# Communicate.net
KiCad netlist of a schematic drawn in Altium Designer
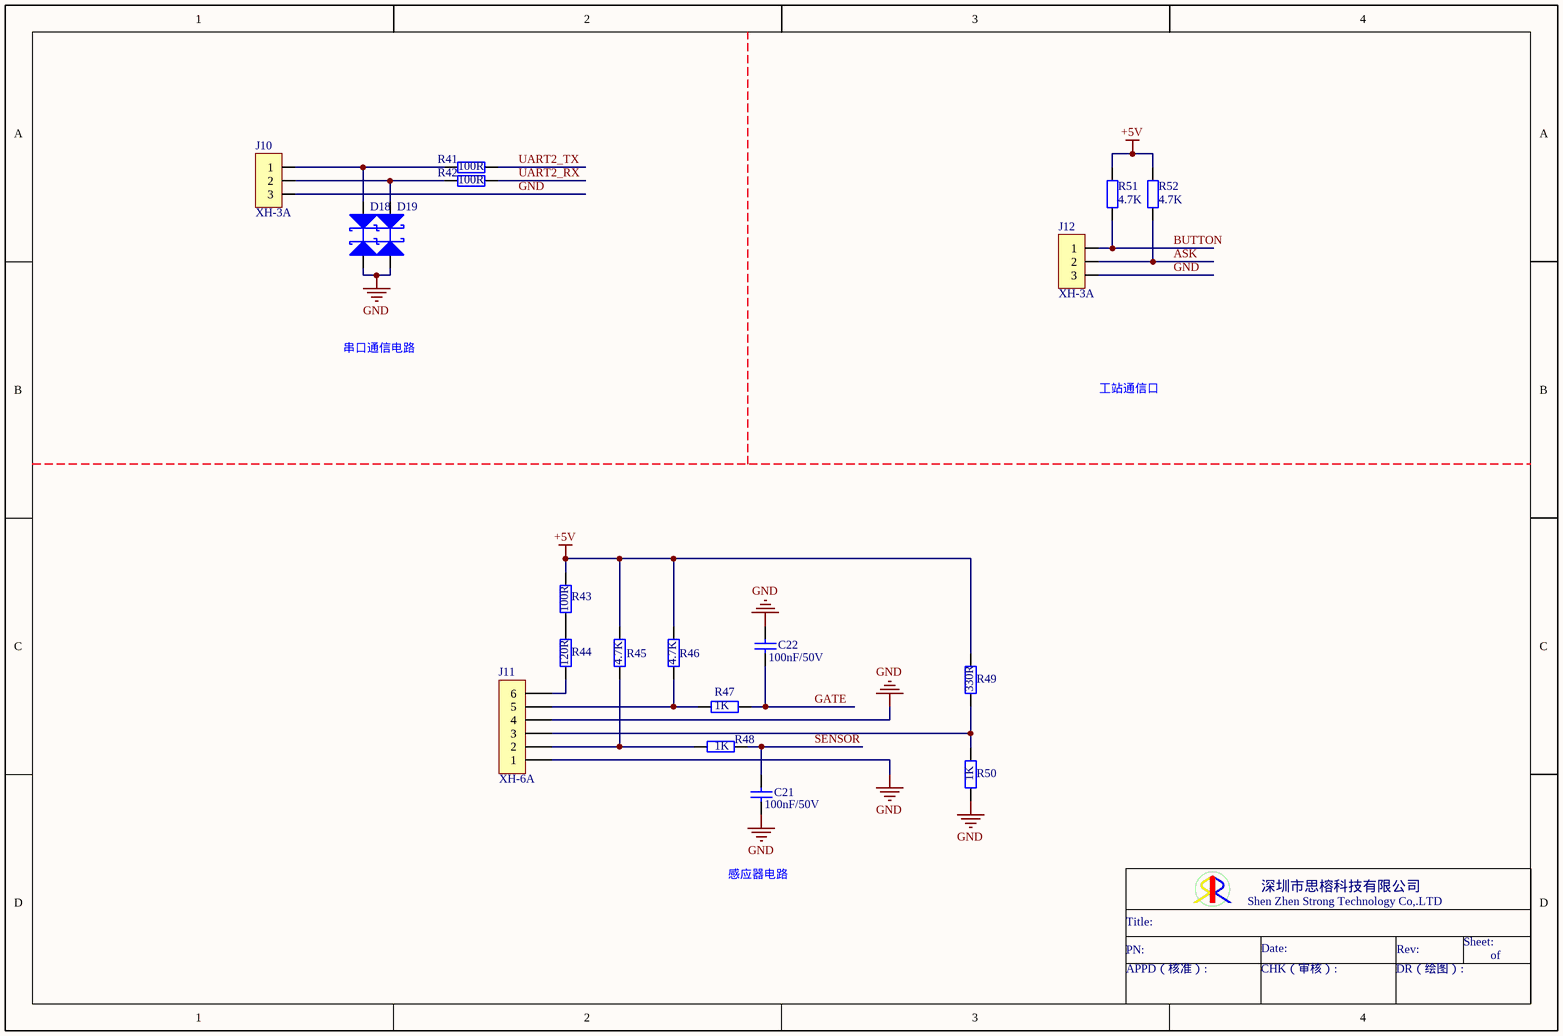
[diagram p0: Communicate.SchDoc]

(export (version "E")
  (design (tool "Eeschema 10.0.6"))
  (components
    (comp (ref "C21")
      (value "100nF/50V")
      (footprint "0603C")
      (description "瓷片电容,100nF,5%,X7R,50V,0603")
      (libsource (lib "SR SCH Library V02") (part "C100nF/50V-0603"))
    )
    (comp (ref "C22")
      (value "100nF/50V")
      (footprint "0603C")
      (description "瓷片电容,100nF,5%,X7R,50V,0603")
      (libsource (lib "SR SCH Library V02") (part "C100nF/50V-0603"))
    )
    (comp (ref "D18")
      (value "ESD5B5.0ST1G")
      (footprint "SOD-523")
      (description "TVS管,5V,SOD-523")
      (libsource (lib "SR SCH Library V02") (part "ESD5B5.0ST1G"))
    )
    (comp (ref "D19")
      (value "ESD5B5.0ST1G")
      (footprint "SOD-523")
      (description "TVS管,5V,SOD-523")
      (libsource (lib "SR SCH Library V02") (part "ESD5B5.0ST1G"))
    )
    (comp (ref "J10")
      (value "XH-3A")
      (footprint "CN3-2.54")
      (description "CONN,XH-3A,3PIN,2.54mm插座")
      (libsource (lib "SR SCH Library V02") (part "CONN-XH-3A"))
    )
    (comp (ref "J11")
      (value "XH-6A")
      (footprint "CN6-2.54")
      (description "CONN,XH-6A,6PIN,2.54mm插座")
      (libsource (lib "SR SCH Library V02") (part "CONN-XH-6A"))
    )
    (comp (ref "J12")
      (value "XH-3A")
      (footprint "CN3-2.54")
      (description "CONN,XH-3A,3PIN,2.54mm插座")
      (libsource (lib "SR SCH Library V02") (part "CONN-XH-3A"))
    )
    (comp (ref "R41")
      (value "100R")
      (footprint "0603R")
      (description "金属膜电阻,100R,1%,1/10W,0603")
      (libsource (lib "SR SCH Library V02") (part "R100R-0603"))
    )
    (comp (ref "R42")
      (value "100R")
      (footprint "0603R")
      (description "金属膜电阻,100R,1%,1/10W,0603")
      (libsource (lib "SR SCH Library V02") (part "R100R-0603"))
    )
    (comp (ref "R43")
      (value "100R")
      (footprint "0603R")
      (description "金属膜电阻,100R,1%,1/10W,0603")
      (libsource (lib "") (part "R100R-0603_1"))
    )
    (comp (ref "R44")
      (value "120R")
      (footprint "0603R")
      (description "金属膜电阻,120R,5W,5%")
      (libsource (lib "SR SCH Library V02") (part "R120R"))
    )
    (comp (ref "R45")
      (value "4.7K")
      (footprint "0603R")
      (description "金属膜电阻,4.7K,1%,1/10W,0603")
      (libsource (lib "SR SCH Library V02") (part "R4.7K-0603"))
    )
    (comp (ref "R46")
      (value "4.7K")
      (footprint "0603R")
      (description "金属膜电阻,4.7K,1%,1/10W,0603")
      (libsource (lib "SR SCH Library V02") (part "R4.7K-0603"))
    )
    (comp (ref "R47")
      (value "1K")
      (footprint "0603R")
      (description "金属膜电阻,1K,1%,1/10W,0603")
      (libsource (lib "SR SCH Library V02") (part "R1K-0603"))
    )
    (comp (ref "R48")
      (value "1K")
      (footprint "0603R")
      (description "金属膜电阻,1K,1%,1/10W,0603")
      (libsource (lib "SR SCH Library V02") (part "R1K-0603"))
    )
    (comp (ref "R49")
      (value "330R")
      (footprint "0603R")
      (description "金属膜电阻,330R,1%,1/10W,0603")
      (libsource (lib "SR SCH Library V02") (part "R330R-0603"))
    )
    (comp (ref "R50")
      (value "1K")
      (footprint "0603R")
      (description "金属膜电阻,1K,1%,1/10W,0603")
      (libsource (lib "") (part "R1K-0603_1"))
    )
    (comp (ref "R51")
      (value "4.7K")
      (footprint "0603R")
      (description "金属膜电阻,4.7K,1%,1/10W,0603")
      (libsource (lib "SR SCH Library V02") (part "R4.7K-0603"))
    )
    (comp (ref "R52")
      (value "4.7K")
      (footprint "0603R")
      (description "金属膜电阻,4.7K,1%,1/10W,0603")
      (libsource (lib "SR SCH Library V02") (part "R4.7K-0603"))
    )
  )
  (nets
    (net (code "1") (name "+5V") (class "Default")
      (node (ref "R43") (pin "2") (pinfunction "2_2") (pintype "passive"))
      (node (ref "R45") (pin "2") (pinfunction "2_2") (pintype "passive"))
      (node (ref "R46") (pin "2") (pinfunction "2_2") (pintype "passive"))
      (node (ref "R49") (pin "2") (pinfunction "2_2") (pintype "passive"))
      (node (ref "R51") (pin "2") (pinfunction "2_2") (pintype "passive"))
      (node (ref "R52") (pin "2") (pinfunction "2_2") (pintype "passive"))
    )
    (net (code "2") (name "/ASK") (class "Default")
      (node (ref "J12") (pin "2") (pinfunction "2_2") (pintype "passive"))
      (node (ref "R52") (pin "1") (pinfunction "1_1") (pintype "passive"))
    )
    (net (code "3") (name "/BUTTON") (class "Default")
      (node (ref "J12") (pin "1") (pinfunction "1_1") (pintype "passive"))
      (node (ref "R51") (pin "1") (pinfunction "1_1") (pintype "passive"))
    )
    (net (code "4") (name "/GATE") (class "Default")
      (node (ref "C22") (pin "2") (pinfunction "2_2") (pintype "passive"))
      (node (ref "R47") (pin "2") (pinfunction "2_2") (pintype "passive"))
    )
    (net (code "5") (name "/SENSOR") (class "Default")
      (node (ref "C21") (pin "2") (pinfunction "2_2") (pintype "passive"))
      (node (ref "R48") (pin "2") (pinfunction "2_2") (pintype "passive"))
    )
    (net (code "6") (name "/UART2_RX") (class "Default")
      (node (ref "R42") (pin "2") (pinfunction "2_2") (pintype "passive"))
    )
    (net (code "7") (name "/UART2_TX") (class "Default")
      (node (ref "R41") (pin "2") (pinfunction "2_2") (pintype "passive"))
    )
    (net (code "8") (name "GND") (class "Default")
      (node (ref "C21") (pin "1") (pinfunction "1_1") (pintype "passive"))
      (node (ref "C22") (pin "1") (pinfunction "1_1") (pintype "passive"))
      (node (ref "D18") (pin "1") (pinfunction "1_1") (pintype "passive"))
      (node (ref "D19") (pin "1") (pinfunction "1_1") (pintype "passive"))
      (node (ref "J10") (pin "3") (pinfunction "3_3") (pintype "passive"))
      (node (ref "J11") (pin "1") (pinfunction "1_1") (pintype "passive"))
      (node (ref "J11") (pin "4") (pinfunction "4_4") (pintype "passive"))
      (node (ref "J12") (pin "3") (pinfunction "3_3") (pintype "passive"))
      (node (ref "R50") (pin "1") (pinfunction "1_1") (pintype "passive"))
    )
    (net (code "9") (name "Net-(D18-Pad2)") (class "Default")
      (node (ref "D18") (pin "2") (pinfunction "2_2") (pintype "passive"))
      (node (ref "J10") (pin "1") (pinfunction "1_1") (pintype "passive"))
      (node (ref "R41") (pin "1") (pinfunction "1_1") (pintype "passive"))
    )
    (net (code "10") (name "Net-(D19-Pad2)") (class "Default")
      (node (ref "D19") (pin "2") (pinfunction "2_2") (pintype "passive"))
      (node (ref "J10") (pin "2") (pinfunction "2_2") (pintype "passive"))
      (node (ref "R42") (pin "1") (pinfunction "1_1") (pintype "passive"))
    )
    (net (code "11") (name "Net-(J11-Pad2)") (class "Default")
      (node (ref "J11") (pin "2") (pinfunction "2_2") (pintype "passive"))
      (node (ref "R45") (pin "1") (pinfunction "1_1") (pintype "passive"))
      (node (ref "R48") (pin "1") (pinfunction "1_1") (pintype "passive"))
    )
    (net (code "12") (name "Net-(J11-Pad3)") (class "Default")
      (node (ref "J11") (pin "3") (pinfunction "3_3") (pintype "passive"))
      (node (ref "R49") (pin "1") (pinfunction "1_1") (pintype "passive"))
      (node (ref "R50") (pin "2") (pinfunction "2_2") (pintype "passive"))
    )
    (net (code "13") (name "Net-(J11-Pad5)") (class "Default")
      (node (ref "J11") (pin "5") (pinfunction "5_5") (pintype "passive"))
      (node (ref "R46") (pin "1") (pinfunction "1_1") (pintype "passive"))
      (node (ref "R47") (pin "1") (pinfunction "1_1") (pintype "passive"))
    )
    (net (code "14") (name "Net-(J11-Pad6)") (class "Default")
      (node (ref "J11") (pin "6") (pinfunction "6_6") (pintype "passive"))
      (node (ref "R44") (pin "1") (pinfunction "1_1") (pintype "passive"))
    )
    (net (code "15") (name "Net-(R43-Pad1)") (class "Default")
      (node (ref "R43") (pin "1") (pinfunction "1_1") (pintype "passive"))
      (node (ref "R44") (pin "2") (pinfunction "2_2") (pintype "passive"))
    )
  )
)
